# Outputs.net
KiCad netlist of a schematic drawn in Altium Designer
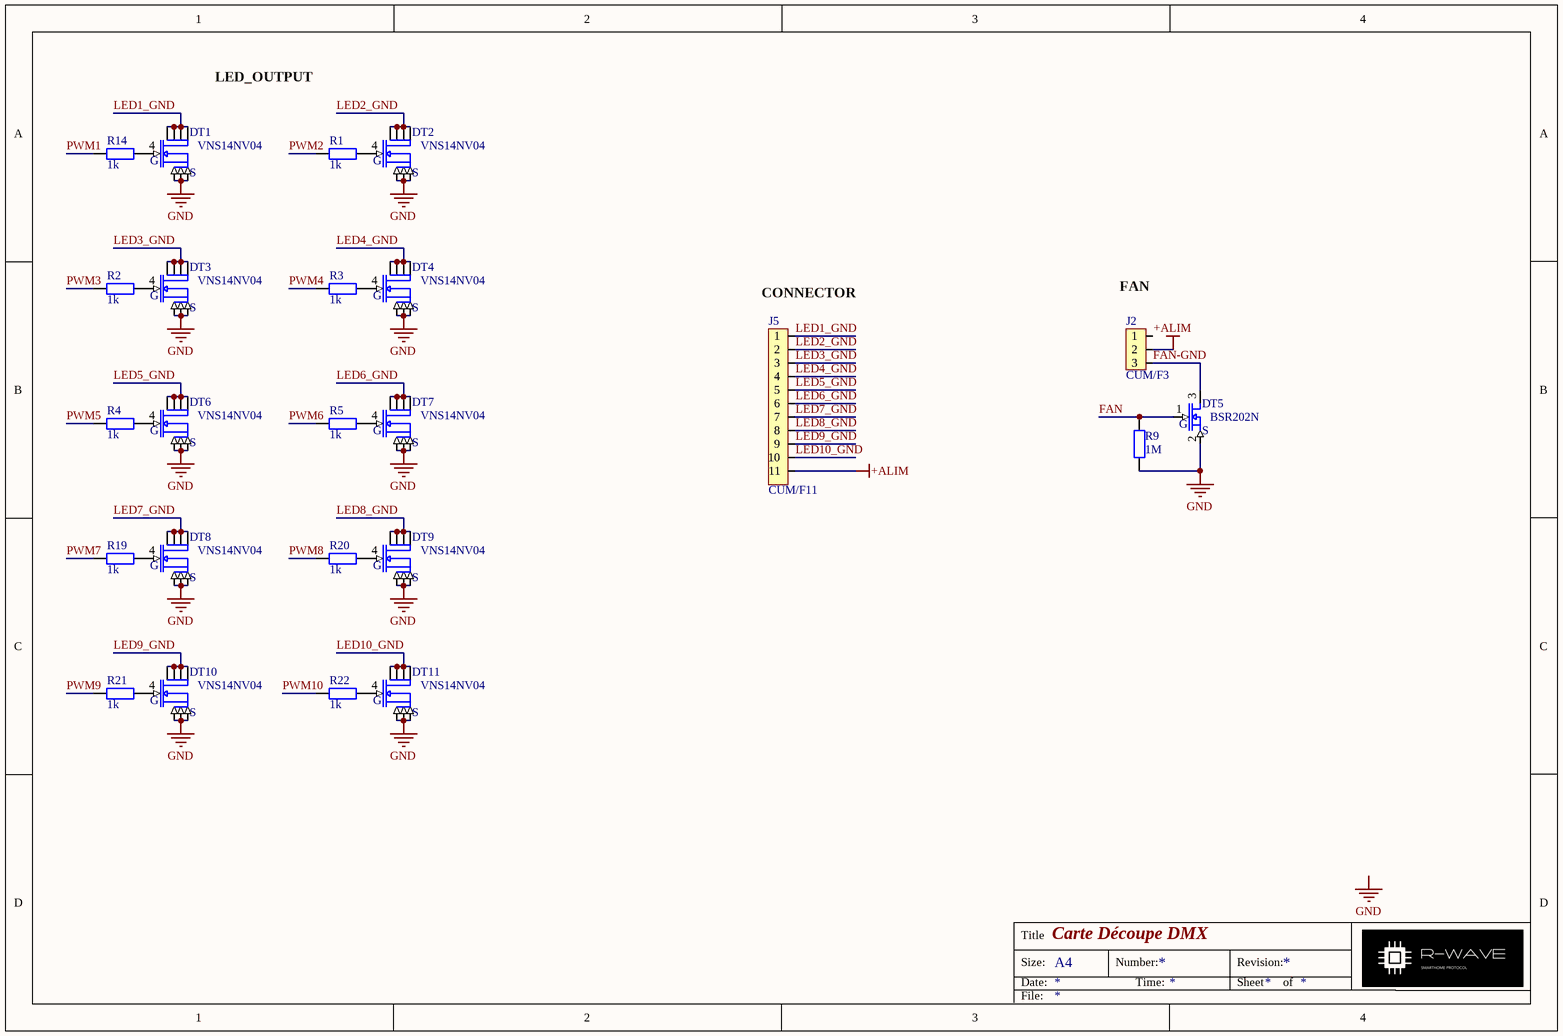
[diagram p0: Outputs.SchDoc]

(export (version "E")
  (design (tool "Eeschema 10.0.6"))
  (components
    (comp (ref "J2")
      (value "CUM/F3")
      (footprint "HDR1X3")
      (description "connecteur 3 points")
      (libsource (lib "PROTEL") (part "CUM/F3"))
    )
    (comp (ref "J5")
      (value "CUM/F11")
      (footprint "CNT11D")
      (description "connecteur 10 points")
      (libsource (lib "PROTEL") (part "CUM/F11"))
    )
    (comp (ref "R1")
      (value "1k")
      (footprint "R0603")
      (description "Thin Metal Film Resistor")
      (libsource (lib "MyLibrary") (part "Res"))
    )
    (comp (ref "R2")
      (value "1k")
      (footprint "R0603")
      (description "Thin Metal Film Resistor")
      (libsource (lib "MyLibrary") (part "Res"))
    )
    (comp (ref "R3")
      (value "1k")
      (footprint "R0603")
      (description "Thin Metal Film Resistor")
      (libsource (lib "MyLibrary") (part "Res"))
    )
    (comp (ref "R4")
      (value "1k")
      (footprint "R0603")
      (description "Thin Metal Film Resistor")
      (libsource (lib "MyLibrary") (part "Res"))
    )
    (comp (ref "R5")
      (value "1k")
      (footprint "R0603")
      (description "Thin Metal Film Resistor")
      (libsource (lib "MyLibrary") (part "Res"))
    )
    (comp (ref "R9")
      (value "1M")
      (footprint "R0603")
      (description "Thin Metal Film Resistor")
      (libsource (lib "") (part "Res_1"))
    )
    (comp (ref "R14")
      (value "1k")
      (footprint "R0603")
      (description "Thin Metal Film Resistor")
      (libsource (lib "MyLibrary") (part "Res"))
    )
    (comp (ref "R19")
      (value "1k")
      (footprint "R0603")
      (description "Thin Metal Film Resistor")
      (libsource (lib "MyLibrary") (part "Res"))
    )
    (comp (ref "R20")
      (value "1k")
      (footprint "R0603")
      (description "Thin Metal Film Resistor")
      (libsource (lib "MyLibrary") (part "Res"))
    )
    (comp (ref "R21")
      (value "1k")
      (footprint "R0603")
      (description "Thin Metal Film Resistor")
      (libsource (lib "MyLibrary") (part "Res"))
    )
    (comp (ref "R22")
      (value "1k")
      (footprint "R0603")
      (description "Thin Metal Film Resistor")
      (libsource (lib "MyLibrary") (part "Res"))
    )
    (comp (ref "T1")
      (value "VNS14NV04")
      (footprint "TRA14NV04")
      (description "TRANSISTOR MOS N")
      (libsource (lib "PROTEL") (part "VNS14NV04"))
    )
    (comp (ref "T2")
      (value "VNS14NV04")
      (footprint "TRA14NV04")
      (description "TRANSISTOR MOS N")
      (libsource (lib "PROTEL") (part "VNS14NV04"))
    )
    (comp (ref "T3")
      (value "VNS14NV04")
      (footprint "TRA14NV04")
      (description "TRANSISTOR MOS N")
      (libsource (lib "PROTEL") (part "VNS14NV04"))
    )
    (comp (ref "T4")
      (value "VNS14NV04")
      (footprint "TRA14NV04")
      (description "TRANSISTOR MOS N")
      (libsource (lib "PROTEL") (part "VNS14NV04"))
    )
    (comp (ref "T5")
      (value "BSR202N")
      (footprint "TRA202")
      (description "TRANSISTOR MOS N")
      (libsource (lib "PROTEL") (part "BSR202N"))
    )
    (comp (ref "T6")
      (value "VNS14NV04")
      (footprint "TRA14NV04")
      (description "TRANSISTOR MOS N")
      (libsource (lib "PROTEL") (part "VNS14NV04"))
    )
    (comp (ref "T7")
      (value "VNS14NV04")
      (footprint "TRA14NV04")
      (description "TRANSISTOR MOS N")
      (libsource (lib "PROTEL") (part "VNS14NV04"))
    )
    (comp (ref "T8")
      (value "VNS14NV04")
      (footprint "TRA14NV04")
      (description "TRANSISTOR MOS N")
      (libsource (lib "PROTEL") (part "VNS14NV04"))
    )
    (comp (ref "T9")
      (value "VNS14NV04")
      (footprint "TRA14NV04")
      (description "TRANSISTOR MOS N")
      (libsource (lib "PROTEL") (part "VNS14NV04"))
    )
    (comp (ref "T10")
      (value "VNS14NV04")
      (footprint "TRA14NV04")
      (description "TRANSISTOR MOS N")
      (libsource (lib "PROTEL") (part "VNS14NV04"))
    )
    (comp (ref "T11")
      (value "VNS14NV04")
      (footprint "TRA14NV04")
      (description "TRANSISTOR MOS N")
      (libsource (lib "PROTEL") (part "VNS14NV04"))
    )
  )
  (nets
    (net (code "1") (name "+ALIM") (class "Default")
      (node (ref "J2") (pin "2") (pinfunction "2_2") (pintype "passive"))
      (node (ref "J5") (pin "11") (pinfunction "11_11") (pintype "passive"))
    )
    (net (code "2") (name "/FAN") (class "Default")
      (node (ref "R9") (pin "2") (pinfunction "2_2") (pintype "passive"))
      (node (ref "T5") (pin "1") (pinfunction "G_1") (pintype "input"))
    )
    (net (code "3") (name "/FAN-GND") (class "Default")
      (node (ref "J2") (pin "3") (pinfunction "3_3") (pintype "passive"))
      (node (ref "T5") (pin "3") (pinfunction "D_3") (pintype "passive"))
    )
    (net (code "4") (name "/LED1_GND") (class "Default")
      (node (ref "J5") (pin "1") (pinfunction "1_1") (pintype "passive"))
      (node (ref "T1") (pin "5") (pinfunction "5_5") (pintype "passive"))
      (node (ref "T1") (pin "6") (pinfunction "6_6") (pintype "passive"))
      (node (ref "T1") (pin "7") (pinfunction "7_7") (pintype "passive"))
      (node (ref "T1") (pin "8") (pinfunction "8_8") (pintype "passive"))
    )
    (net (code "5") (name "/LED2_GND") (class "Default")
      (node (ref "J5") (pin "2") (pinfunction "2_2") (pintype "passive"))
      (node (ref "T2") (pin "5") (pinfunction "5_5") (pintype "passive"))
      (node (ref "T2") (pin "6") (pinfunction "6_6") (pintype "passive"))
      (node (ref "T2") (pin "7") (pinfunction "7_7") (pintype "passive"))
      (node (ref "T2") (pin "8") (pinfunction "8_8") (pintype "passive"))
    )
    (net (code "6") (name "/LED3_GND") (class "Default")
      (node (ref "J5") (pin "3") (pinfunction "3_3") (pintype "passive"))
      (node (ref "T3") (pin "5") (pinfunction "5_5") (pintype "passive"))
      (node (ref "T3") (pin "6") (pinfunction "6_6") (pintype "passive"))
      (node (ref "T3") (pin "7") (pinfunction "7_7") (pintype "passive"))
      (node (ref "T3") (pin "8") (pinfunction "8_8") (pintype "passive"))
    )
    (net (code "7") (name "/LED4_GND") (class "Default")
      (node (ref "J5") (pin "4") (pinfunction "4_4") (pintype "passive"))
      (node (ref "T4") (pin "5") (pinfunction "5_5") (pintype "passive"))
      (node (ref "T4") (pin "6") (pinfunction "6_6") (pintype "passive"))
      (node (ref "T4") (pin "7") (pinfunction "7_7") (pintype "passive"))
      (node (ref "T4") (pin "8") (pinfunction "8_8") (pintype "passive"))
    )
    (net (code "8") (name "/LED5_GND") (class "Default")
      (node (ref "J5") (pin "5") (pinfunction "5_5") (pintype "passive"))
      (node (ref "T6") (pin "5") (pinfunction "5_5") (pintype "passive"))
      (node (ref "T6") (pin "6") (pinfunction "6_6") (pintype "passive"))
      (node (ref "T6") (pin "7") (pinfunction "7_7") (pintype "passive"))
      (node (ref "T6") (pin "8") (pinfunction "8_8") (pintype "passive"))
    )
    (net (code "9") (name "/LED6_GND") (class "Default")
      (node (ref "J5") (pin "6") (pinfunction "6_6") (pintype "passive"))
      (node (ref "T7") (pin "5") (pinfunction "5_5") (pintype "passive"))
      (node (ref "T7") (pin "6") (pinfunction "6_6") (pintype "passive"))
      (node (ref "T7") (pin "7") (pinfunction "7_7") (pintype "passive"))
      (node (ref "T7") (pin "8") (pinfunction "8_8") (pintype "passive"))
    )
    (net (code "10") (name "/LED7_GND") (class "Default")
      (node (ref "J5") (pin "7") (pinfunction "7_7") (pintype "passive"))
      (node (ref "T8") (pin "5") (pinfunction "5_5") (pintype "passive"))
      (node (ref "T8") (pin "6") (pinfunction "6_6") (pintype "passive"))
      (node (ref "T8") (pin "7") (pinfunction "7_7") (pintype "passive"))
      (node (ref "T8") (pin "8") (pinfunction "8_8") (pintype "passive"))
    )
    (net (code "11") (name "/LED8_GND") (class "Default")
      (node (ref "J5") (pin "8") (pinfunction "8_8") (pintype "passive"))
      (node (ref "T9") (pin "5") (pinfunction "5_5") (pintype "passive"))
      (node (ref "T9") (pin "6") (pinfunction "6_6") (pintype "passive"))
      (node (ref "T9") (pin "7") (pinfunction "7_7") (pintype "passive"))
      (node (ref "T9") (pin "8") (pinfunction "8_8") (pintype "passive"))
    )
    (net (code "12") (name "/LED9_GND") (class "Default")
      (node (ref "J5") (pin "9") (pinfunction "9_9") (pintype "passive"))
      (node (ref "T10") (pin "5") (pinfunction "5_5") (pintype "passive"))
      (node (ref "T10") (pin "6") (pinfunction "6_6") (pintype "passive"))
      (node (ref "T10") (pin "7") (pinfunction "7_7") (pintype "passive"))
      (node (ref "T10") (pin "8") (pinfunction "8_8") (pintype "passive"))
    )
    (net (code "13") (name "/LED10_GND") (class "Default")
      (node (ref "J5") (pin "10") (pinfunction "10_10") (pintype "passive"))
      (node (ref "T11") (pin "5") (pinfunction "5_5") (pintype "passive"))
      (node (ref "T11") (pin "6") (pinfunction "6_6") (pintype "passive"))
      (node (ref "T11") (pin "7") (pinfunction "7_7") (pintype "passive"))
      (node (ref "T11") (pin "8") (pinfunction "8_8") (pintype "passive"))
    )
    (net (code "14") (name "/PWM1") (class "Default")
      (node (ref "R14") (pin "2") (pinfunction "2_2") (pintype "passive"))
    )
    (net (code "15") (name "/PWM2") (class "Default")
      (node (ref "R1") (pin "2") (pinfunction "2_2") (pintype "passive"))
    )
    (net (code "16") (name "/PWM3") (class "Default")
      (node (ref "R2") (pin "2") (pinfunction "2_2") (pintype "passive"))
    )
    (net (code "17") (name "/PWM4") (class "Default")
      (node (ref "R3") (pin "2") (pinfunction "2_2") (pintype "passive"))
    )
    (net (code "18") (name "/PWM5") (class "Default")
      (node (ref "R4") (pin "2") (pinfunction "2_2") (pintype "passive"))
    )
    (net (code "19") (name "/PWM6") (class "Default")
      (node (ref "R5") (pin "2") (pinfunction "2_2") (pintype "passive"))
    )
    (net (code "20") (name "/PWM7") (class "Default")
      (node (ref "R19") (pin "2") (pinfunction "2_2") (pintype "passive"))
    )
    (net (code "21") (name "/PWM8") (class "Default")
      (node (ref "R20") (pin "2") (pinfunction "2_2") (pintype "passive"))
    )
    (net (code "22") (name "/PWM9") (class "Default")
      (node (ref "R21") (pin "2") (pinfunction "2_2") (pintype "passive"))
    )
    (net (code "23") (name "/PWM10") (class "Default")
      (node (ref "R22") (pin "2") (pinfunction "2_2") (pintype "passive"))
    )
    (net (code "24") (name "GND") (class "Default")
      (node (ref "R9") (pin "1") (pinfunction "1_1") (pintype "passive"))
      (node (ref "T1") (pin "1") (pinfunction "1_1") (pintype "input"))
      (node (ref "T1") (pin "2") (pinfunction "2_2") (pintype "input"))
      (node (ref "T1") (pin "3") (pinfunction "3_3") (pintype "input"))
      (node (ref "T10") (pin "1") (pinfunction "1_1") (pintype "input"))
      (node (ref "T10") (pin "2") (pinfunction "2_2") (pintype "input"))
      (node (ref "T10") (pin "3") (pinfunction "3_3") (pintype "input"))
      (node (ref "T11") (pin "1") (pinfunction "1_1") (pintype "input"))
      (node (ref "T11") (pin "2") (pinfunction "2_2") (pintype "input"))
      (node (ref "T11") (pin "3") (pinfunction "3_3") (pintype "input"))
      (node (ref "T2") (pin "1") (pinfunction "1_1") (pintype "input"))
      (node (ref "T2") (pin "2") (pinfunction "2_2") (pintype "input"))
      (node (ref "T2") (pin "3") (pinfunction "3_3") (pintype "input"))
      (node (ref "T3") (pin "1") (pinfunction "1_1") (pintype "input"))
      (node (ref "T3") (pin "2") (pinfunction "2_2") (pintype "input"))
      (node (ref "T3") (pin "3") (pinfunction "3_3") (pintype "input"))
      (node (ref "T4") (pin "1") (pinfunction "1_1") (pintype "input"))
      (node (ref "T4") (pin "2") (pinfunction "2_2") (pintype "input"))
      (node (ref "T4") (pin "3") (pinfunction "3_3") (pintype "input"))
      (node (ref "T5") (pin "2") (pinfunction "S_2") (pintype "input"))
      (node (ref "T6") (pin "1") (pinfunction "1_1") (pintype "input"))
      (node (ref "T6") (pin "2") (pinfunction "2_2") (pintype "input"))
      (node (ref "T6") (pin "3") (pinfunction "3_3") (pintype "input"))
      (node (ref "T7") (pin "1") (pinfunction "1_1") (pintype "input"))
      (node (ref "T7") (pin "2") (pinfunction "2_2") (pintype "input"))
      (node (ref "T7") (pin "3") (pinfunction "3_3") (pintype "input"))
      (node (ref "T8") (pin "1") (pinfunction "1_1") (pintype "input"))
      (node (ref "T8") (pin "2") (pinfunction "2_2") (pintype "input"))
      (node (ref "T8") (pin "3") (pinfunction "3_3") (pintype "input"))
      (node (ref "T9") (pin "1") (pinfunction "1_1") (pintype "input"))
      (node (ref "T9") (pin "2") (pinfunction "2_2") (pintype "input"))
      (node (ref "T9") (pin "3") (pinfunction "3_3") (pintype "input"))
    )
    (net (code "25") (name "Net-(R1-Pad1)") (class "Default")
      (node (ref "R1") (pin "1") (pinfunction "1_1") (pintype "passive"))
      (node (ref "T2") (pin "4") (pinfunction "4_4") (pintype "input"))
    )
    (net (code "26") (name "Net-(R2-Pad1)") (class "Default")
      (node (ref "R2") (pin "1") (pinfunction "1_1") (pintype "passive"))
      (node (ref "T3") (pin "4") (pinfunction "4_4") (pintype "input"))
    )
    (net (code "27") (name "Net-(R3-Pad1)") (class "Default")
      (node (ref "R3") (pin "1") (pinfunction "1_1") (pintype "passive"))
      (node (ref "T4") (pin "4") (pinfunction "4_4") (pintype "input"))
    )
    (net (code "28") (name "Net-(R4-Pad1)") (class "Default")
      (node (ref "R4") (pin "1") (pinfunction "1_1") (pintype "passive"))
      (node (ref "T6") (pin "4") (pinfunction "4_4") (pintype "input"))
    )
    (net (code "29") (name "Net-(R5-Pad1)") (class "Default")
      (node (ref "R5") (pin "1") (pinfunction "1_1") (pintype "passive"))
      (node (ref "T7") (pin "4") (pinfunction "4_4") (pintype "input"))
    )
    (net (code "30") (name "Net-(R14-Pad1)") (class "Default")
      (node (ref "R14") (pin "1") (pinfunction "1_1") (pintype "passive"))
      (node (ref "T1") (pin "4") (pinfunction "4_4") (pintype "input"))
    )
    (net (code "31") (name "Net-(R19-Pad1)") (class "Default")
      (node (ref "R19") (pin "1") (pinfunction "1_1") (pintype "passive"))
      (node (ref "T8") (pin "4") (pinfunction "4_4") (pintype "input"))
    )
    (net (code "32") (name "Net-(R20-Pad1)") (class "Default")
      (node (ref "R20") (pin "1") (pinfunction "1_1") (pintype "passive"))
      (node (ref "T9") (pin "4") (pinfunction "4_4") (pintype "input"))
    )
    (net (code "33") (name "Net-(R21-Pad1)") (class "Default")
      (node (ref "R21") (pin "1") (pinfunction "1_1") (pintype "passive"))
      (node (ref "T10") (pin "4") (pinfunction "4_4") (pintype "input"))
    )
    (net (code "34") (name "Net-(R22-Pad1)") (class "Default")
      (node (ref "R22") (pin "1") (pinfunction "1_1") (pintype "passive"))
      (node (ref "T11") (pin "4") (pinfunction "4_4") (pintype "input"))
    )
    (net (code "35") (name "unconnected-(J2-Pad1)") (class "Default")
      (node (ref "J2") (pin "1") (pinfunction "1_1") (pintype "passive"))
    )
  )
)
